# 03_Incense_4G.net
KiCad netlist of a schematic drawn in Altium Designer
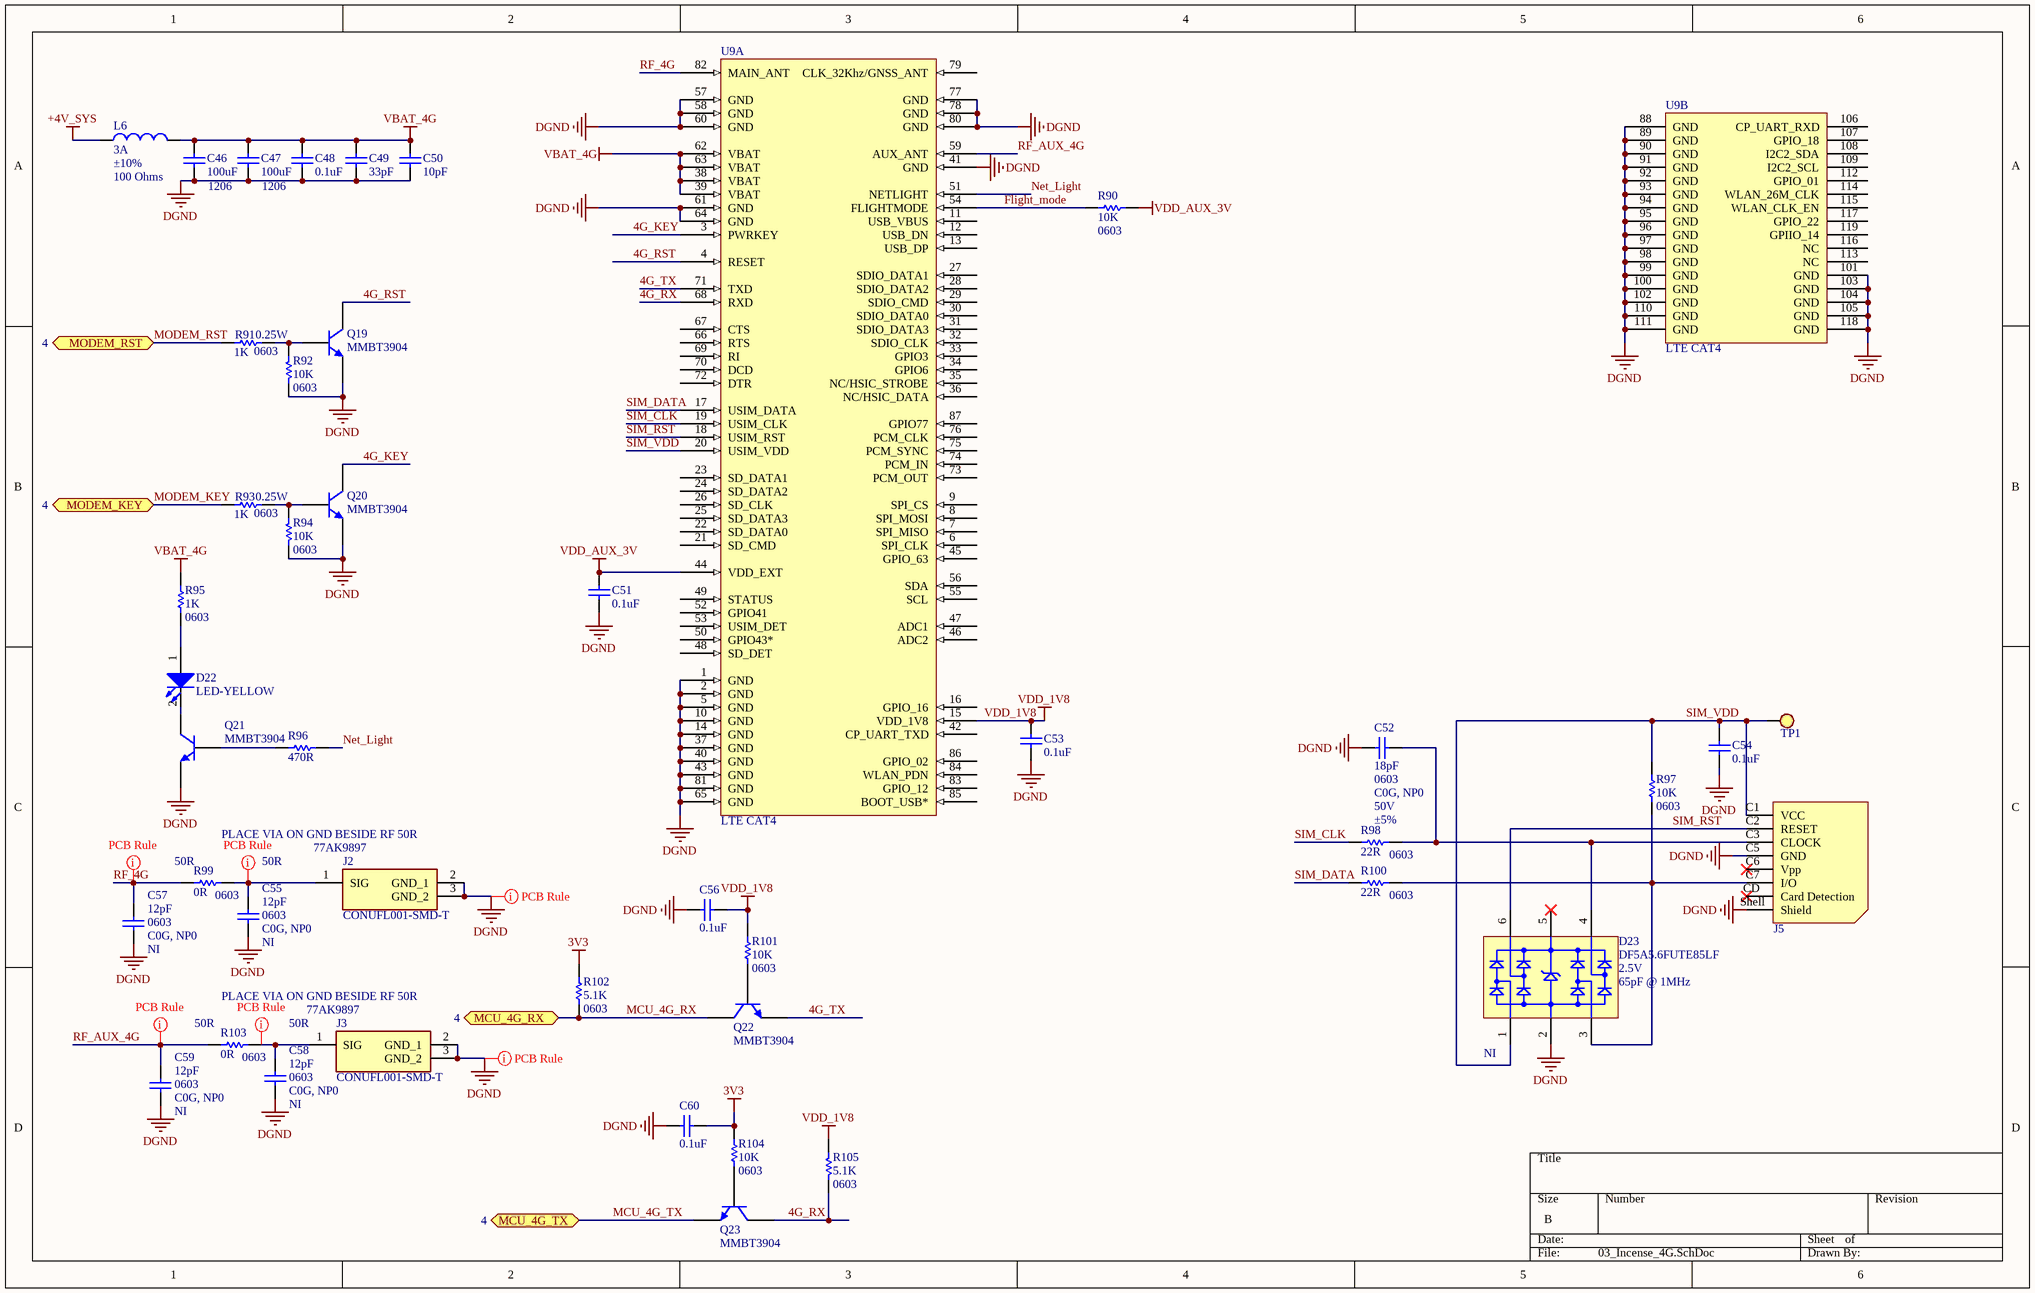
[diagram p0: 03_Incense_4G.SchDoc]

(export (version "E")
  (design (tool "Eeschema 10.0.6"))
  (components
    (comp (ref "C46")
      (value "100uF")
      (footprint "CAP 1206")
      (description "CAP CER 100UF 6.3V X5R 1206")
      (fields
        (field (name "VOLTAGE") "6.3V")
        (field (name "PCB FOOTPRINT") "1206")
        (field (name "TOLERANCE") "±10%")
      )
      (libsource (lib "Slider") (part "Cap"))
    )
    (comp (ref "C47")
      (value "100uF")
      (footprint "CAP 1206")
      (description "CAP CER 100UF 6.3V X5R 1206")
      (fields
        (field (name "VOLTAGE") "6.3V")
        (field (name "PCB FOOTPRINT") "1206")
        (field (name "TOLERANCE") "±10%")
      )
      (libsource (lib "Slider") (part "Cap"))
    )
    (comp (ref "C48")
      (value "0.1uF")
      (footprint "CAP 0603")
      (description "CAP-CER,SMD;0.1UF,10%,50V,X7R,0603")
      (fields (field (name "VOLTAGE") "50V") (field (name "TOLERANCE") "±10%"))
      (libsource (lib "Slider") (part "Cap"))
    )
    (comp (ref "C49")
      (value "33pF")
      (footprint "CAP 0603")
      (description "CAP CER 33PF 50V C0G/NPO 0603")
      (fields (field (name "VOLTAGE") "50V") (field (name "TOLERANCE") "±10%"))
      (libsource (lib "Slider") (part "Cap"))
    )
    (comp (ref "C50")
      (value "10pF")
      (footprint "CAP 0603")
      (description "CAP CER 10PF 50V C0G/NPO 0603")
      (fields (field (name "VOLTAGE") "50V") (field (name "TOLERANCE") "±10%"))
      (libsource (lib "Slider") (part "Cap"))
    )
    (comp (ref "C51")
      (value "0.1uF")
      (footprint "CAP 0603")
      (description "CAP-CER,SMD;0.1UF,10%,50V,X7R,0603")
      (fields (field (name "VOLTAGE") "50V") (field (name "TOLERANCE") "±10%"))
      (libsource (lib "Slider") (part "Cap"))
    )
    (comp (ref "C52")
      (value "18pF")
      (footprint "0603")
      (description "CAP CER 18PF 50V C0G/NP0 0603")
      (fields
        (field (name "MATERIAL") "C0G, NP0")
        (field (name "VOLTAGE") "50V")
        (field (name "TOLERANCE") "±5%")
        (field (name "MANUFACTURER1_PART#") "CL10C180JB81PNC")
        (field (name "MANUFACTURER2_PART#") "CC0603JRNPO9BN180")
      )
      (libsource (lib "Slider") (part "Cap"))
    )
    (comp (ref "C53")
      (value "0.1uF")
      (footprint "CAP 0603")
      (description "CAP-CER,SMD;0.1UF,10%,50V,X7R,0603")
      (fields (field (name "VOLTAGE") "50V") (field (name "TOLERANCE") "±10%"))
      (libsource (lib "Slider") (part "Cap"))
    )
    (comp (ref "C54")
      (value "0.1uF")
      (footprint "CAP 0603")
      (description "CAP-CER,SMD;0.1UF,10%,50V,X7R,0603")
      (fields (field (name "VOLTAGE") "50V") (field (name "TOLERANCE") "±10%"))
      (libsource (lib "Slider") (part "Cap"))
    )
    (comp (ref "C55")
      (value "12pF")
      (footprint "0603")
      (description "CAP-CER,SMD;12PF,5%,50V,C0G/NPO 0603")
      (fields
        (field (name "NI_MARK") "NI")
        (field (name "MATERIAL") "C0G, NP0")
        (field (name "VOLTAGE") "50V")
        (field (name "TOLERANCE") "±5%")
      )
      (libsource (lib "Slider") (part "Cap"))
    )
    (comp (ref "C56")
      (value "0.1uF")
      (footprint "CAP 0603")
      (description "CAP-CER,SMD;0.1UF,10%,50V,X7R,0603")
      (fields (field (name "VOLTAGE") "50V") (field (name "TOLERANCE") "±10%"))
      (libsource (lib "Slider") (part "Cap"))
    )
    (comp (ref "C57")
      (value "12pF")
      (footprint "0603")
      (description "CAP-CER,SMD;12PF,5%,50V,C0G/NPO 0603")
      (fields
        (field (name "NI_MARK") "NI")
        (field (name "MATERIAL") "C0G, NP0")
        (field (name "VOLTAGE") "50V")
        (field (name "TOLERANCE") "±5%")
      )
      (libsource (lib "Slider") (part "Cap"))
    )
    (comp (ref "C58")
      (value "12pF")
      (footprint "0603")
      (description "CAP-CER,SMD;12PF,5%,50V,C0G/NPO 0603")
      (fields
        (field (name "NI_MARK") "NI")
        (field (name "MATERIAL") "C0G, NP0")
        (field (name "VOLTAGE") "50V")
        (field (name "TOLERANCE") "±5%")
      )
      (libsource (lib "Slider") (part "Cap"))
    )
    (comp (ref "C59")
      (value "12pF")
      (footprint "0603")
      (description "CAP-CER,SMD;12PF,5%,50V,C0G/NPO 0603")
      (fields
        (field (name "NI_MARK") "NI")
        (field (name "MATERIAL") "C0G, NP0")
        (field (name "VOLTAGE") "50V")
        (field (name "TOLERANCE") "±5%")
      )
      (libsource (lib "Slider") (part "Cap"))
    )
    (comp (ref "C60")
      (value "0.1uF")
      (footprint "CAP 0603")
      (description "CAP-CER,SMD;0.1UF,10%,50V,X7R,0603")
      (fields (field (name "VOLTAGE") "50V") (field (name "TOLERANCE") "±10%"))
      (libsource (lib "Slider") (part "Cap"))
    )
    (comp (ref "D22")
      (value "LED-YELLOW")
      (footprint "LED 0603")
      (description "LED-SMD,2V,20mA,0603,RED")
      (fields
        (field (name "MANUFACTURER2_PART#") "LTST-S270KSKT")
        (field (name "MANUFACTURER1_PART#") "LY Q396-P1Q2-36")
      )
      (libsource (lib "VSM_SES-MAIN_REV04B") (part "LED-RED"))
    )
    (comp (ref "D23")
      (value "DF5A5.6FUTE85LF")
      (footprint "SC-70-6")
      (description "2.5V TVS DIODE SOT23-6")
      (fields
        (field (name "VOLTAGE") "2.5V")
        (field (name "CAPACITANCE") "65pF @ 1MHz")
        (field (name "NI_MARK") "NI")
      )
      (libsource (lib "My Library") (part "DIODES 5v TVS SOT-23-6"))
    )
    (comp (ref "J2")
      (value "CONUFL001-SMD-T")
      (footprint "CONUFL001-SMD")
      (description "RF Connectors / Coaxial Connectors T&R U.FL Straight Surface Mount Jack")
      (fields
        (field (name "MANUFACTURER2_PART#") "712-CONUFL001-SMD-T")
        (field (name "SUPPLIER PART NUMBER 1") "77AK9897")
      )
      (libsource (lib "*") (part "CONUFL001-SMD-T"))
    )
    (comp (ref "J3")
      (value "CONUFL001-SMD-T")
      (footprint "CONUFL001-SMD")
      (description "RF Connectors / Coaxial Connectors T&R U.FL Straight Surface Mount Jack")
      (fields
        (field (name "MANUFACTURER2_PART#") "712-CONUFL001-SMD-T")
        (field (name "SUPPLIER PART NUMBER 1") "77AK9897")
      )
      (libsource (lib "*") (part "CONUFL001-SMD-T"))
    )
    (comp (ref "J5")
      (value "693021020811")
      (footprint "693021020811")
      (description "WR-CRD_SMT_MICROSIM_PUSH&PUSH_CD")
      (fields (field (name "MANUFACTURER") "Wurth Elektronik"))
      (libsource (lib "Altium_WR-CRD (rev23b)") (part "693021020811"))
    )
    (comp (ref "L6")
      (value "100 Ohms")
      (footprint "FB 0603")
      (description "FERRITE BEAD 100 OHM 0603 1LN")
      (fields
        (field (name "MANUFACTURER1_PART#") "MPZ1608S101ATAH0")
        (field (name "MANUFACTURER2_PART#") "BLM18KG101TN1D")
        (field (name "CURRENT") "3A")
        (field (name "TOLERANCE") "±10%")
      )
      (libsource (lib "Full") (part "inductor 2.2uF"))
    )
    (comp (ref "Q19")
      (value "MMBT3904")
      (footprint "SOT-23")
      (description "NPN 200mA 40V 350mW SOT-23 Transistors")
      (libsource (lib "") (part "NPN_1"))
    )
    (comp (ref "Q20")
      (value "MMBT3904")
      (footprint "SOT-23")
      (description "NPN 200mA 40V 350mW SOT-23 Transistors")
      (libsource (lib "") (part "NPN_1"))
    )
    (comp (ref "Q21")
      (value "MMBT3904")
      (footprint "SOT-23")
      (description "NPN 200mA 40V 350mW SOT-23 Transistors")
      (libsource (lib "") (part "NPN_1"))
    )
    (comp (ref "Q22")
      (value "MMBT3904")
      (footprint "SOT-23")
      (description "NPN 200mA 40V 350mW SOT-23 Transistors")
      (libsource (lib "Miscellaneous Devices") (part "NPN"))
    )
    (comp (ref "Q23")
      (value "MMBT3904")
      (footprint "SOT-23")
      (description "NPN 200mA 40V 350mW SOT-23 Transistors")
      (libsource (lib "Miscellaneous Devices") (part "NPN"))
    )
    (comp (ref "R90")
      (value "10K")
      (footprint "res 0603")
      (description "RES SMD,10K OHM 5% 1/10W 0603")
      (fields
        (field (name "MANUFACTURER1_PART#") "RMCF0603JT10K0")
        (field (name "MANUFACTURER2_PART#") "R0603J10KKDX")
        (field (name "PCB FOOTPRINT") "0603")
      )
      (libsource (lib "altium-import") (part "root_2_Res0.3_"))
    )
    (comp (ref "R91")
      (value "1K")
      (footprint "res 0603")
      (description "RES SMD,1K OHM,5%,1/10W,0603")
      (fields
        (field (name "MANUFACTURER1_PART#") "RMCF06031K00JNEAC")
        (field (name "MANUFACTURER2_PART#") "R0603J1KTG")
        (field (name "PCB FOOTPRINT") "0603")
        (field (name "POWER") "0.25W")
      )
      (libsource (lib "Full") (part "Res0.3"))
    )
    (comp (ref "R92")
      (value "10K")
      (footprint "res 0603")
      (description "RES SMD,10K OHM 5% 1/10W 0603")
      (fields
        (field (name "MANUFACTURER1_PART#") "RMCF0603JT10K0")
        (field (name "MANUFACTURER2_PART#") "R0603J10KKDX")
        (field (name "PCB FOOTPRINT") "0603")
      )
      (libsource (lib "altium-import") (part "root_3_mirrored_Res0.3_"))
    )
    (comp (ref "R93")
      (value "1K")
      (footprint "res 0603")
      (description "RES SMD,1K OHM,5%,1/10W,0603")
      (fields
        (field (name "MANUFACTURER1_PART#") "RMCF06031K00JNEAC")
        (field (name "MANUFACTURER2_PART#") "R0603J1KTG")
        (field (name "PCB FOOTPRINT") "0603")
        (field (name "POWER") "0.25W")
      )
      (libsource (lib "Full") (part "Res0.3"))
    )
    (comp (ref "R94")
      (value "10K")
      (footprint "res 0603")
      (description "RES SMD,10K OHM 5% 1/10W 0603")
      (fields
        (field (name "MANUFACTURER1_PART#") "RMCF0603JT10K0")
        (field (name "MANUFACTURER2_PART#") "R0603J10KKDX")
        (field (name "PCB FOOTPRINT") "0603")
      )
      (libsource (lib "altium-import") (part "root_3_mirrored_Res0.3_"))
    )
    (comp (ref "R95")
      (value "1K")
      (footprint "res 0603")
      (description "RES SMD,1K OHM,5%,1/10W,0603")
      (fields
        (field (name "MANUFACTURER1_PART#") "RMCF06031K00JNEAC")
        (field (name "MANUFACTURER2_PART#") "R0603J1KTG")
        (field (name "PCB FOOTPRINT") "0603")
      )
      (libsource (lib "Full") (part "Res0.3"))
    )
    (comp (ref "R96")
      (value "470R")
      (footprint "res 0603")
      (description "RES SMD, 470 OHM 5% 1/8W 0603")
      (fields
        (field (name "MANUFACTURER1_PART#") "RK73B1JTTD471J")
        (field (name "MANUFACTURER2_PART#") "RMCF0603JT470R")
      )
      (libsource (lib "Full") (part "Res0.3"))
    )
    (comp (ref "R97")
      (value "10K")
      (footprint "res 0603")
      (description "RES SMD,10K OHM 5% 1/10W 0603")
      (fields
        (field (name "MANUFACTURER1_PART#") "RMCF0603JT10K0")
        (field (name "MANUFACTURER2_PART#") "R0603J10KKDX")
        (field (name "PCB FOOTPRINT") "0603")
      )
      (libsource (lib "altium-import") (part "root_3_Res0.3_"))
    )
    (comp (ref "R98")
      (value "22R")
      (footprint "res 0603")
      (description "RES 22 OHM 5% 1/10W 0603")
      (fields
        (field (name "MANUFACTURER1_PART#") "RC0603JR-0722RL")
        (field (name "MANUFACTURER2_PART#") "RMCF0603JT22R0")
        (field (name "PCB FOOTPRINT") "0603")
      )
      (libsource (lib "Full") (part "Res0.3"))
    )
    (comp (ref "R99")
      (value "0R")
      (footprint "res 0603")
      (description "RES SMD 0 OHM JUMPER 1/10W 0603")
      (fields
        (field (name "MANUFACTURER1_PART#") "RC0603JR-070RL")
        (field (name "MANUFACTURER2_PART#") "RMCF0603ZT0R00")
        (field (name "PCB FOOTPRINT") "0603")
      )
      (libsource (lib "Full") (part "Res0.3"))
    )
    (comp (ref "R100")
      (value "22R")
      (footprint "res 0603")
      (description "RES 22 OHM 5% 1/10W 0603")
      (fields
        (field (name "MANUFACTURER1_PART#") "RC0603JR-0722RL")
        (field (name "MANUFACTURER2_PART#") "RMCF0603JT22R0")
        (field (name "PCB FOOTPRINT") "0603")
      )
      (libsource (lib "Full") (part "Res0.3"))
    )
    (comp (ref "R101")
      (value "10K")
      (footprint "res 0603")
      (description "RES SMD,10K OHM 5% 1/10W 0603")
      (fields
        (field (name "MANUFACTURER1_PART#") "RMCF0603JT10K0")
        (field (name "MANUFACTURER2_PART#") "R0603J10KKDX")
        (field (name "PCB FOOTPRINT") "0603")
      )
      (libsource (lib "altium-import") (part "root_3_Res0.3_"))
    )
    (comp (ref "R102")
      (value "5.1K")
      (footprint "res 0603")
      (description "RES SMD 5.1K OHM 1% 1/10W 0603")
      (fields (field (name "MANUFACTURER1_PART#") "RC0603FR-075K1L") (field (name "PCB FOOTPRINT") "0603"))
      (libsource (lib "Full") (part "Res0.3"))
    )
    (comp (ref "R103")
      (value "0R")
      (footprint "res 0603")
      (description "RES SMD 0 OHM JUMPER 1/10W 0603")
      (fields
        (field (name "MANUFACTURER1_PART#") "RC0603JR-070RL")
        (field (name "MANUFACTURER2_PART#") "RMCF0603ZT0R00")
        (field (name "PCB FOOTPRINT") "0603")
      )
      (libsource (lib "Full") (part "Res0.3"))
    )
    (comp (ref "R104")
      (value "10K")
      (footprint "res 0603")
      (description "RES SMD,10K OHM 5% 1/10W 0603")
      (fields
        (field (name "MANUFACTURER1_PART#") "RMCF0603JT10K0")
        (field (name "MANUFACTURER2_PART#") "R0603J10KKDX")
        (field (name "PCB FOOTPRINT") "0603")
      )
      (libsource (lib "altium-import") (part "root_3_Res0.3_"))
    )
    (comp (ref "R105")
      (value "5.1K")
      (footprint "res 0603")
      (description "RES SMD 5.1K OHM 1% 1/10W 0603")
      (fields (field (name "MANUFACTURER1_PART#") "RC0603FR-075K1L") (field (name "PCB FOOTPRINT") "0603"))
      (libsource (lib "Full") (part "Res0.3"))
    )
    (comp (ref "TP1")
      (value "TP SMD")
      (footprint "TESTPOINT")
      (description "TEST POINT")
      (libsource (lib "VSM") (part "TP SMD"))
    )
    (comp (ref "U9")
      (value "LTE CAT4")
      (footprint "SIM7600C_L1")
      (description "MODULE 4G SIM7600C_L1")
      (fields (field (name "MANUFACTURER1_PART#") "A7600C-L1"))
      (libsource (lib "lib") (part "SIM7600C_L1"))
    )
  )
  (nets
    (net (code "1") (name "+4V_SYS") (class "Default")
      (node (ref "L6") (pin "1") (pinfunction "1_1") (pintype "passive"))
    )
    (net (code "2") (name "/4G_KEY") (class "Default")
      (node (ref "Q20") (pin "3") (pinfunction "C_3") (pintype "passive"))
      (node (ref "U9") (pin "3") (pinfunction "PWRKEY_3") (pintype "input"))
    )
    (net (code "3") (name "/4G_RST") (class "Default")
      (node (ref "Q19") (pin "3") (pinfunction "C_3") (pintype "passive"))
      (node (ref "U9") (pin "4") (pinfunction "RESET_4") (pintype "input"))
    )
    (net (code "4") (name "/4G_RX") (class "Default")
      (node (ref "Q23") (pin "3") (pinfunction "C_3") (pintype "passive"))
      (node (ref "R105") (pin "2") (pinfunction "2_2") (pintype "passive"))
      (node (ref "U9") (pin "68") (pinfunction "RXD_68") (pintype "input"))
    )
    (net (code "5") (name "/4G_TX") (class "Default")
      (node (ref "Q22") (pin "2") (pinfunction "E_2") (pintype "passive"))
      (node (ref "U9") (pin "71") (pinfunction "TXD_71") (pintype "input"))
    )
    (net (code "6") (name "/Flight_mode") (class "Default")
      (node (ref "R90") (pin "2") (pinfunction "2_2") (pintype "passive"))
      (node (ref "U9") (pin "54") (pinfunction "FLIGHTMODE_54") (pintype "input"))
    )
    (net (code "7") (name "/MCU_4G_RX") (class "Default")
      (node (ref "Q22") (pin "3") (pinfunction "C_3") (pintype "passive"))
      (node (ref "R102") (pin "2") (pinfunction "2_2") (pintype "passive"))
    )
    (net (code "8") (name "/MCU_4G_TX") (class "Default")
      (node (ref "Q23") (pin "2") (pinfunction "E_2") (pintype "passive"))
    )
    (net (code "9") (name "/MODEM_KEY") (class "Default")
      (node (ref "R93") (pin "2") (pinfunction "2_2") (pintype "passive"))
    )
    (net (code "10") (name "/MODEM_RST") (class "Default")
      (node (ref "R91") (pin "2") (pinfunction "2_2") (pintype "passive"))
    )
    (net (code "11") (name "/Net_Light") (class "Default")
      (node (ref "R96") (pin "2") (pinfunction "2_2") (pintype "passive"))
      (node (ref "U9") (pin "51") (pinfunction "NETLIGHT_51") (pintype "input"))
    )
    (net (code "12") (name "/RF_4G") (class "Default")
      (node (ref "C57") (pin "1") (pinfunction "1_1") (pintype "passive"))
      (node (ref "R99") (pin "1") (pinfunction "1_1") (pintype "passive"))
      (node (ref "U9") (pin "82") (pinfunction "MAIN_ANT_82") (pintype "input"))
    )
    (net (code "13") (name "/RF_AUX_4G") (class "Default")
      (node (ref "C59") (pin "1") (pinfunction "1_1") (pintype "passive"))
      (node (ref "R103") (pin "1") (pinfunction "1_1") (pintype "passive"))
      (node (ref "U9") (pin "59") (pinfunction "AUX_ANT_59") (pintype "input"))
    )
    (net (code "14") (name "/SIM_CLK") (class "Default")
      (node (ref "R98") (pin "1") (pinfunction "1_1") (pintype "passive"))
      (node (ref "U9") (pin "19") (pinfunction "USIM_CLK_19") (pintype "input"))
    )
    (net (code "15") (name "/SIM_DATA") (class "Default")
      (node (ref "R100") (pin "1") (pinfunction "1_1") (pintype "passive"))
      (node (ref "U9") (pin "17") (pinfunction "USIM_DATA_17") (pintype "input"))
    )
    (net (code "16") (name "/SIM_RST") (class "Default")
      (node (ref "D23") (pin "6") (pinfunction "I/O_4_6") (pintype "passive"))
      (node (ref "J5") (pin "C2") (pinfunction "RESET_C2") (pintype "passive"))
      (node (ref "U9") (pin "18") (pinfunction "USIM_RST_18") (pintype "input"))
    )
    (net (code "17") (name "/SIM_VDD") (class "Default")
      (node (ref "C54") (pin "1") (pinfunction "1_1") (pintype "passive"))
      (node (ref "D23") (pin "1") (pinfunction "I/O_1_1") (pintype "passive"))
      (node (ref "J5") (pin "C1") (pinfunction "VCC_C1") (pintype "passive"))
      (node (ref "R97") (pin "1") (pinfunction "1_1") (pintype "passive"))
      (node (ref "TP1") (pin "1") (pinfunction "1_1") (pintype "passive"))
      (node (ref "U9") (pin "20") (pinfunction "USIM_VDD_20") (pintype "input"))
    )
    (net (code "18") (name "3V3") (class "Default")
      (node (ref "C60") (pin "2") (pinfunction "2_2") (pintype "passive"))
      (node (ref "R102") (pin "1") (pinfunction "1_1") (pintype "passive"))
      (node (ref "R104") (pin "1") (pinfunction "1_1") (pintype "passive"))
    )
    (net (code "19") (name "DGND") (class "Default")
      (node (ref "C46") (pin "2") (pinfunction "2_2") (pintype "passive"))
      (node (ref "C47") (pin "2") (pinfunction "2_2") (pintype "passive"))
      (node (ref "C48") (pin "2") (pinfunction "2_2") (pintype "passive"))
      (node (ref "C49") (pin "2") (pinfunction "2_2") (pintype "passive"))
      (node (ref "C50") (pin "2") (pinfunction "2_2") (pintype "passive"))
      (node (ref "C51") (pin "2") (pinfunction "2_2") (pintype "passive"))
      (node (ref "C52") (pin "2") (pinfunction "2_2") (pintype "passive"))
      (node (ref "C53") (pin "2") (pinfunction "2_2") (pintype "passive"))
      (node (ref "C54") (pin "2") (pinfunction "2_2") (pintype "passive"))
      (node (ref "C55") (pin "2") (pinfunction "2_2") (pintype "passive"))
      (node (ref "C56") (pin "2") (pinfunction "2_2") (pintype "passive"))
      (node (ref "C57") (pin "2") (pinfunction "2_2") (pintype "passive"))
      (node (ref "C58") (pin "2") (pinfunction "2_2") (pintype "passive"))
      (node (ref "C59") (pin "2") (pinfunction "2_2") (pintype "passive"))
      (node (ref "C60") (pin "1") (pinfunction "1_1") (pintype "passive"))
      (node (ref "D23") (pin "2") (pinfunction "GND_2") (pintype "passive"))
      (node (ref "J2") (pin "2") (pinfunction "GND_1_2") (pintype "passive"))
      (node (ref "J2") (pin "3") (pinfunction "GND_2_3") (pintype "passive"))
      (node (ref "J3") (pin "2") (pinfunction "GND_1_2") (pintype "passive"))
      (node (ref "J3") (pin "3") (pinfunction "GND_2_3") (pintype "passive"))
      (node (ref "J5") (pin "C5") (pinfunction "GND_C5") (pintype "passive"))
      (node (ref "J5") (pin "Shell") (pinfunction "Shield_Shell") (pintype "passive"))
      (node (ref "Q19") (pin "2") (pinfunction "E_2") (pintype "passive"))
      (node (ref "Q20") (pin "2") (pinfunction "E_2") (pintype "passive"))
      (node (ref "Q21") (pin "2") (pinfunction "E_2") (pintype "passive"))
      (node (ref "R92") (pin "2") (pinfunction "2_2") (pintype "passive"))
      (node (ref "R94") (pin "2") (pinfunction "2_2") (pintype "passive"))
      (node (ref "U9") (pin "1") (pinfunction "GND_1") (pintype "input"))
      (node (ref "U9") (pin "10") (pinfunction "GND_10") (pintype "input"))
      (node (ref "U9") (pin "100") (pinfunction "GND_100") (pintype "passive"))
      (node (ref "U9") (pin "101") (pinfunction "GND_101") (pintype "passive"))
      (node (ref "U9") (pin "102") (pinfunction "GND_102") (pintype "passive"))
      (node (ref "U9") (pin "103") (pinfunction "GND_103") (pintype "passive"))
      (node (ref "U9") (pin "104") (pinfunction "GND_104") (pintype "passive"))
      (node (ref "U9") (pin "105") (pinfunction "GND_105") (pintype "passive"))
      (node (ref "U9") (pin "110") (pinfunction "GND_110") (pintype "passive"))
      (node (ref "U9") (pin "111") (pinfunction "GND_111") (pintype "passive"))
      (node (ref "U9") (pin "118") (pinfunction "GND_118") (pintype "passive"))
      (node (ref "U9") (pin "14") (pinfunction "GND_14") (pintype "input"))
      (node (ref "U9") (pin "2") (pinfunction "GND_2") (pintype "input"))
      (node (ref "U9") (pin "37") (pinfunction "GND_37") (pintype "input"))
      (node (ref "U9") (pin "40") (pinfunction "GND_40") (pintype "input"))
      (node (ref "U9") (pin "41") (pinfunction "GND_41") (pintype "input"))
      (node (ref "U9") (pin "43") (pinfunction "GND_43") (pintype "input"))
      (node (ref "U9") (pin "5") (pinfunction "GND_5") (pintype "input"))
      (node (ref "U9") (pin "57") (pinfunction "GND_57") (pintype "input"))
      (node (ref "U9") (pin "58") (pinfunction "GND_58") (pintype "input"))
      (node (ref "U9") (pin "60") (pinfunction "GND_60") (pintype "input"))
      (node (ref "U9") (pin "61") (pinfunction "GND_61") (pintype "input"))
      (node (ref "U9") (pin "64") (pinfunction "GND_64") (pintype "input"))
      (node (ref "U9") (pin "65") (pinfunction "GND_65") (pintype "input"))
      (node (ref "U9") (pin "77") (pinfunction "GND_77") (pintype "input"))
      (node (ref "U9") (pin "78") (pinfunction "GND_78") (pintype "input"))
      (node (ref "U9") (pin "80") (pinfunction "GND_80") (pintype "input"))
      (node (ref "U9") (pin "81") (pinfunction "GND_81") (pintype "input"))
      (node (ref "U9") (pin "88") (pinfunction "GND_88") (pintype "passive"))
      (node (ref "U9") (pin "89") (pinfunction "GND_89") (pintype "passive"))
      (node (ref "U9") (pin "90") (pinfunction "GND_90") (pintype "passive"))
      (node (ref "U9") (pin "91") (pinfunction "GND_91") (pintype "passive"))
      (node (ref "U9") (pin "92") (pinfunction "GND_92") (pintype "passive"))
      (node (ref "U9") (pin "93") (pinfunction "GND_93") (pintype "passive"))
      (node (ref "U9") (pin "94") (pinfunction "GND_94") (pintype "passive"))
      (node (ref "U9") (pin "95") (pinfunction "GND_95") (pintype "passive"))
      (node (ref "U9") (pin "96") (pinfunction "GND_96") (pintype "passive"))
      (node (ref "U9") (pin "97") (pinfunction "GND_97") (pintype "passive"))
      (node (ref "U9") (pin "98") (pinfunction "GND_98") (pintype "passive"))
      (node (ref "U9") (pin "99") (pinfunction "GND_99") (pintype "passive"))
    )
    (net (code "20") (name "Net-(D22-A)") (class "Default")
      (node (ref "D22") (pin "1") (pinfunction "A_1") (pintype "passive"))
      (node (ref "R95") (pin "1") (pinfunction "1_1") (pintype "passive"))
    )
    (net (code "21") (name "Net-(D22-K)") (class "Default")
      (node (ref "D22") (pin "2") (pinfunction "K_2") (pintype "passive"))
      (node (ref "Q21") (pin "3") (pinfunction "C_3") (pintype "passive"))
    )
    (net (code "22") (name "Net-(D23-I{slash}O_2)") (class "Default")
      (node (ref "D23") (pin "3") (pinfunction "I/O_2_3") (pintype "passive"))
      (node (ref "J5") (pin "C7") (pinfunction "I/O_C7") (pintype "passive"))
      (node (ref "R100") (pin "2") (pinfunction "2_2") (pintype "passive"))
      (node (ref "R97") (pin "2") (pinfunction "2_2") (pintype "passive"))
    )
    (net (code "23") (name "Net-(D23-I{slash}O_3)") (class "Default")
      (node (ref "C52") (pin "1") (pinfunction "1_1") (pintype "passive"))
      (node (ref "D23") (pin "4") (pinfunction "I/O_3_4") (pintype "passive"))
      (node (ref "J5") (pin "C3") (pinfunction "CLOCK_C3") (pintype "passive"))
      (node (ref "R98") (pin "2") (pinfunction "2_2") (pintype "passive"))
    )
    (net (code "24") (name "Net-(J2-SIG)") (class "Default")
      (node (ref "C55") (pin "1") (pinfunction "1_1") (pintype "passive"))
      (node (ref "J2") (pin "1") (pinfunction "SIG_1") (pintype "passive"))
      (node (ref "R99") (pin "2") (pinfunction "2_2") (pintype "passive"))
    )
    (net (code "25") (name "Net-(J3-SIG)") (class "Default")
      (node (ref "C58") (pin "1") (pinfunction "1_1") (pintype "passive"))
      (node (ref "J3") (pin "1") (pinfunction "SIG_1") (pintype "passive"))
      (node (ref "R103") (pin "2") (pinfunction "2_2") (pintype "passive"))
    )
    (net (code "26") (name "Net-(Q19-B)") (class "Default")
      (node (ref "Q19") (pin "1") (pinfunction "B_1") (pintype "passive"))
      (node (ref "R91") (pin "1") (pinfunction "1_1") (pintype "passive"))
      (node (ref "R92") (pin "1") (pinfunction "1_1") (pintype "passive"))
    )
    (net (code "27") (name "Net-(Q20-B)") (class "Default")
      (node (ref "Q20") (pin "1") (pinfunction "B_1") (pintype "passive"))
      (node (ref "R93") (pin "1") (pinfunction "1_1") (pintype "passive"))
      (node (ref "R94") (pin "1") (pinfunction "1_1") (pintype "passive"))
    )
    (net (code "28") (name "Net-(Q21-B)") (class "Default")
      (node (ref "Q21") (pin "1") (pinfunction "B_1") (pintype "passive"))
      (node (ref "R96") (pin "1") (pinfunction "1_1") (pintype "passive"))
    )
    (net (code "29") (name "Net-(Q22-B)") (class "Default")
      (node (ref "Q22") (pin "1") (pinfunction "B_1") (pintype "passive"))
      (node (ref "R101") (pin "2") (pinfunction "2_2") (pintype "passive"))
    )
    (net (code "30") (name "Net-(Q23-B)") (class "Default")
      (node (ref "Q23") (pin "1") (pinfunction "B_1") (pintype "passive"))
      (node (ref "R104") (pin "2") (pinfunction "2_2") (pintype "passive"))
    )
    (net (code "31") (name "VBAT_4G") (class "Default")
      (node (ref "C46") (pin "1") (pinfunction "1_1") (pintype "passive"))
      (node (ref "C47") (pin "1") (pinfunction "1_1") (pintype "passive"))
      (node (ref "C48") (pin "1") (pinfunction "1_1") (pintype "passive"))
      (node (ref "C49") (pin "1") (pinfunction "1_1") (pintype "passive"))
      (node (ref "C50") (pin "1") (pinfunction "1_1") (pintype "passive"))
      (node (ref "L6") (pin "2") (pinfunction "2_2") (pintype "passive"))
      (node (ref "R95") (pin "2") (pinfunction "2_2") (pintype "passive"))
      (node (ref "U9") (pin "38") (pinfunction "VBAT_38") (pintype "input"))
      (node (ref "U9") (pin "39") (pinfunction "VBAT_39") (pintype "input"))
      (node (ref "U9") (pin "62") (pinfunction "VBAT_62") (pintype "input"))
      (node (ref "U9") (pin "63") (pinfunction "VBAT_63") (pintype "input"))
    )
    (net (code "32") (name "VDD_1V8") (class "Default")
      (node (ref "C53") (pin "1") (pinfunction "1_1") (pintype "passive"))
      (node (ref "C56") (pin "1") (pinfunction "1_1") (pintype "passive"))
      (node (ref "R101") (pin "1") (pinfunction "1_1") (pintype "passive"))
      (node (ref "R105") (pin "1") (pinfunction "1_1") (pintype "passive"))
      (node (ref "U9") (pin "15") (pinfunction "VDD_1V8_15") (pintype "input"))
    )
    (net (code "33") (name "VDD_AUX_3V") (class "Default")
      (node (ref "C51") (pin "1") (pinfunction "1_1") (pintype "passive"))
      (node (ref "R90") (pin "1") (pinfunction "1_1") (pintype "passive"))
      (node (ref "U9") (pin "44") (pinfunction "VDD_EXT_44") (pintype "input"))
    )
    (net (code "34") (name "unconnected-(D23-VBUS-Pad5)") (class "Default")
      (node (ref "D23") (pin "5") (pinfunction "VBUS_5") (pintype "passive+no_connect"))
    )
    (net (code "35") (name "unconnected-(J5-Card_Detection-PadCD)") (class "Default")
      (node (ref "J5") (pin "CD") (pinfunction "Card_Detection_CD") (pintype "passive+no_connect"))
    )
    (net (code "36") (name "unconnected-(J5-Vpp-PadC6)") (class "Default")
      (node (ref "J5") (pin "C6") (pinfunction "Vpp_C6") (pintype "passive+no_connect"))
    )
    (net (code "37") (name "unconnected-(U9A-ADC1-Pad47)") (class "Default")
      (node (ref "U9") (pin "47") (pinfunction "ADC1_47") (pintype "input"))
    )
    (net (code "38") (name "unconnected-(U9A-ADC2-Pad46)") (class "Default")
      (node (ref "U9") (pin "46") (pinfunction "ADC2_46") (pintype "input"))
    )
    (net (code "39") (name "unconnected-(U9A-BOOT_USB*-Pad85)") (class "Default")
      (node (ref "U9") (pin "85") (pinfunction "BOOT_USB*_85") (pintype "input"))
    )
    (net (code "40") (name "unconnected-(U9A-CLK_32Khz{slash}GNSS_ANT-Pad79)") (class "Default")
      (node (ref "U9") (pin "79") (pinfunction "CLK_32Khz/GNSS_ANT_79") (pintype "input"))
    )
    (net (code "41") (name "unconnected-(U9A-CP_UART_TXD-Pad42)") (class "Default")
      (node (ref "U9") (pin "42") (pinfunction "CP_UART_TXD_42") (pintype "input"))
    )
    (net (code "42") (name "unconnected-(U9A-CTS-Pad67)") (class "Default")
      (node (ref "U9") (pin "67") (pinfunction "CTS_67") (pintype "input"))
    )
    (net (code "43") (name "unconnected-(U9A-DCD-Pad70)") (class "Default")
      (node (ref "U9") (pin "70") (pinfunction "DCD_70") (pintype "input"))
    )
    (net (code "44") (name "unconnected-(U9A-DTR-Pad72)") (class "Default")
      (node (ref "U9") (pin "72") (pinfunction "DTR_72") (pintype "input"))
    )
    (net (code "45") (name "unconnected-(U9A-GPIO3-Pad33)") (class "Default")
      (node (ref "U9") (pin "33") (pinfunction "GPIO3_33") (pintype "input"))
    )
    (net (code "46") (name "unconnected-(U9A-GPIO6-Pad34)") (class "Default")
      (node (ref "U9") (pin "34") (pinfunction "GPIO6_34") (pintype "input"))
    )
    (net (code "47") (name "unconnected-(U9A-GPIO41-Pad52)") (class "Default")
      (node (ref "U9") (pin "52") (pinfunction "GPIO41_52") (pintype "input"))
    )
    (net (code "48") (name "unconnected-(U9A-GPIO43*-Pad50)") (class "Default")
      (node (ref "U9") (pin "50") (pinfunction "GPIO43*_50") (pintype "input"))
    )
    (net (code "49") (name "unconnected-(U9A-GPIO77-Pad87)") (class "Default")
      (node (ref "U9") (pin "87") (pinfunction "GPIO77_87") (pintype "input"))
    )
    (net (code "50") (name "unconnected-(U9A-GPIO_02-Pad86)") (class "Default")
      (node (ref "U9") (pin "86") (pinfunction "GPIO_02_86") (pintype "input"))
    )
    (net (code "51") (name "unconnected-(U9A-GPIO_12-Pad83)") (class "Default")
      (node (ref "U9") (pin "83") (pinfunction "GPIO_12_83") (pintype "input"))
    )
    (net (code "52") (name "unconnected-(U9A-GPIO_16-Pad16)") (class "Default")
      (node (ref "U9") (pin "16") (pinfunction "GPIO_16_16") (pintype "input"))
    )
    (net (code "53") (name "unconnected-(U9A-GPIO_63-Pad45)") (class "Default")
      (node (ref "U9") (pin "45") (pinfunction "GPIO_63_45") (pintype "input"))
    )
    (net (code "54") (name "unconnected-(U9A-NC{slash}HSIC_DATA-Pad36)") (class "Default")
      (node (ref "U9") (pin "36") (pinfunction "NC/HSIC_DATA_36") (pintype "input"))
    )
    (net (code "55") (name "unconnected-(U9A-NC{slash}HSIC_STROBE-Pad35)") (class "Default")
      (node (ref "U9") (pin "35") (pinfunction "NC/HSIC_STROBE_35") (pintype "input"))
    )
    (net (code "56") (name "unconnected-(U9A-PCM_CLK-Pad76)") (class "Default")
      (node (ref "U9") (pin "76") (pinfunction "PCM_CLK_76") (pintype "input"))
    )
    (net (code "57") (name "unconnected-(U9A-PCM_IN-Pad74)") (class "Default")
      (node (ref "U9") (pin "74") (pinfunction "PCM_IN_74") (pintype "input"))
    )
    (net (code "58") (name "unconnected-(U9A-PCM_OUT-Pad73)") (class "Default")
      (node (ref "U9") (pin "73") (pinfunction "PCM_OUT_73") (pintype "input"))
    )
    (net (code "59") (name "unconnected-(U9A-PCM_SYNC-Pad75)") (class "Default")
      (node (ref "U9") (pin "75") (pinfunction "PCM_SYNC_75") (pintype "input"))
    )
    (net (code "60") (name "unconnected-(U9A-RI-Pad69)") (class "Default")
      (node (ref "U9") (pin "69") (pinfunction "RI_69") (pintype "input"))
    )
    (net (code "61") (name "unconnected-(U9A-RTS-Pad66)") (class "Default")
      (node (ref "U9") (pin "66") (pinfunction "RTS_66") (pintype "input"))
    )
    (net (code "62") (name "unconnected-(U9A-SCL-Pad55)") (class "Default")
      (node (ref "U9") (pin "55") (pinfunction "SCL_55") (pintype "input"))
    )
    (net (code "63") (name "unconnected-(U9A-SDA-Pad56)") (class "Default")
      (node (ref "U9") (pin "56") (pinfunction "SDA_56") (pintype "input"))
    )
    (net (code "64") (name "unconnected-(U9A-SDIO_CLK-Pad32)") (class "Default")
      (node (ref "U9") (pin "32") (pinfunction "SDIO_CLK_32") (pintype "input"))
    )
    (net (code "65") (name "unconnected-(U9A-SDIO_CMD-Pad29)") (class "Default")
      (node (ref "U9") (pin "29") (pinfunction "SDIO_CMD_29") (pintype "input"))
    )
    (net (code "66") (name "unconnected-(U9A-SDIO_DATA0-Pad30)") (class "Default")
      (node (ref "U9") (pin "30") (pinfunction "SDIO_DATA0_30") (pintype "input"))
    )
    (net (code "67") (name "unconnected-(U9A-SDIO_DATA1-Pad27)") (class "Default")
      (node (ref "U9") (pin "27") (pinfunction "SDIO_DATA1_27") (pintype "input"))
    )
    (net (code "68") (name "unconnected-(U9A-SDIO_DATA2-Pad28)") (class "Default")
      (node (ref "U9") (pin "28") (pinfunction "SDIO_DATA2_28") (pintype "input"))
    )
    (net (code "69") (name "unconnected-(U9A-SDIO_DATA3-Pad31)") (class "Default")
      (node (ref "U9") (pin "31") (pinfunction "SDIO_DATA3_31") (pintype "input"))
    )
    (net (code "70") (name "unconnected-(U9A-SD_CLK-Pad26)") (class "Default")
      (node (ref "U9") (pin "26") (pinfunction "SD_CLK_26") (pintype "input"))
    )
    (net (code "71") (name "unconnected-(U9A-SD_CMD-Pad21)") (class "Default")
      (node (ref "U9") (pin "21") (pinfunction "SD_CMD_21") (pintype "input"))
    )
    (net (code "72") (name "unconnected-(U9A-SD_DATA0-Pad22)") (class "Default")
      (node (ref "U9") (pin "22") (pinfunction "SD_DATA0_22") (pintype "input"))
    )
    (net (code "73") (name "unconnected-(U9A-SD_DATA1-Pad23)") (class "Default")
      (node (ref "U9") (pin "23") (pinfunction "SD_DATA1_23") (pintype "input"))
    )
    (net (code "74") (name "unconnected-(U9A-SD_DATA2-Pad24)") (class "Default")
      (node (ref "U9") (pin "24") (pinfunction "SD_DATA2_24") (pintype "input"))
    )
    (net (code "75") (name "unconnected-(U9A-SD_DATA3-Pad25)") (class "Default")
      (node (ref "U9") (pin "25") (pinfunction "SD_DATA3_25") (pintype "input"))
    )
    (net (code "76") (name "unconnected-(U9A-SD_DET-Pad48)") (class "Default")
      (node (ref "U9") (pin "48") (pinfunction "SD_DET_48") (pintype "input"))
    )
    (net (code "77") (name "unconnected-(U9A-SPI_CLK-Pad6)") (class "Default")
      (node (ref "U9") (pin "6") (pinfunction "SPI_CLK_6") (pintype "input"))
    )
    (net (code "78") (name "unconnected-(U9A-SPI_CS-Pad9)") (class "Default")
      (node (ref "U9") (pin "9") (pinfunction "SPI_CS_9") (pintype "input"))
    )
    (net (code "79") (name "unconnected-(U9A-SPI_MISO-Pad7)") (class "Default")
      (node (ref "U9") (pin "7") (pinfunction "SPI_MISO_7") (pintype "input"))
    )
    (net (code "80") (name "unconnected-(U9A-SPI_MOSI-Pad8)") (class "Default")
      (node (ref "U9") (pin "8") (pinfunction "SPI_MOSI_8") (pintype "input"))
    )
    (net (code "81") (name "unconnected-(U9A-STATUS-Pad49)") (class "Default")
      (node (ref "U9") (pin "49") (pinfunction "STATUS_49") (pintype "input"))
    )
    (net (code "82") (name "unconnected-(U9A-USB_DN-Pad12)") (class "Default")
      (node (ref "U9") (pin "12") (pinfunction "USB_DN_12") (pintype "input"))
    )
    (net (code "83") (name "unconnected-(U9A-USB_DP-Pad13)") (class "Default")
      (node (ref "U9") (pin "13") (pinfunction "USB_DP_13") (pintype "input"))
    )
    (net (code "84") (name "unconnected-(U9A-USB_VBUS-Pad11)") (class "Default")
      (node (ref "U9") (pin "11") (pinfunction "USB_VBUS_11") (pintype "input"))
    )
    (net (code "85") (name "unconnected-(U9A-USIM_DET-Pad53)") (class "Default")
      (node (ref "U9") (pin "53") (pinfunction "USIM_DET_53") (pintype "input"))
    )
    (net (code "86") (name "unconnected-(U9A-WLAN_PDN-Pad84)") (class "Default")
      (node (ref "U9") (pin "84") (pinfunction "WLAN_PDN_84") (pintype "input"))
    )
    (net (code "87") (name "unconnected-(U9B-CP_UART_RXD-Pad106)") (class "Default")
      (node (ref "U9") (pin "106") (pinfunction "CP_UART_RXD_106") (pintype "passive"))
    )
    (net (code "88") (name "unconnected-(U9B-GPIIO_14-Pad119)") (class "Default")
      (node (ref "U9") (pin "119") (pinfunction "GPIIO_14_119") (pintype "passive"))
    )
    (net (code "89") (name "unconnected-(U9B-GPIO_01-Pad112)") (class "Default")
      (node (ref "U9") (pin "112") (pinfunction "GPIO_01_112") (pintype "passive"))
    )
    (net (code "90") (name "unconnected-(U9B-GPIO_18-Pad107)") (class "Default")
      (node (ref "U9") (pin "107") (pinfunction "GPIO_18_107") (pintype "passive"))
    )
    (net (code "91") (name "unconnected-(U9B-GPIO_22-Pad117)") (class "Default")
      (node (ref "U9") (pin "117") (pinfunction "GPIO_22_117") (pintype "passive"))
    )
    (net (code "92") (name "unconnected-(U9B-I2C2_SCL-Pad109)") (class "Default")
      (node (ref "U9") (pin "109") (pinfunction "I2C2_SCL_109") (pintype "passive"))
    )
    (net (code "93") (name "unconnected-(U9B-I2C2_SDA-Pad108)") (class "Default")
      (node (ref "U9") (pin "108") (pinfunction "I2C2_SDA_108") (pintype "passive"))
    )
    (net (code "94") (name "unconnected-(U9B-NC-Pad113)") (class "Default")
      (node (ref "U9") (pin "113") (pinfunction "NC_113") (pintype "passive"))
    )
    (net (code "95") (name "unconnected-(U9B-NC-Pad116)") (class "Default")
      (node (ref "U9") (pin "116") (pinfunction "NC_116") (pintype "passive"))
    )
    (net (code "96") (name "unconnected-(U9B-WLAN_26M_CLK-Pad114)") (class "Default")
      (node (ref "U9") (pin "114") (pinfunction "WLAN_26M_CLK_114") (pintype "passive"))
    )
    (net (code "97") (name "unconnected-(U9B-WLAN_CLK_EN-Pad115)") (class "Default")
      (node (ref "U9") (pin "115") (pinfunction "WLAN_CLK_EN_115") (pintype "passive"))
    )
  )
)
